# CPU_22032016_v2.net
KiCad netlist of a schematic drawn in Altium Designer
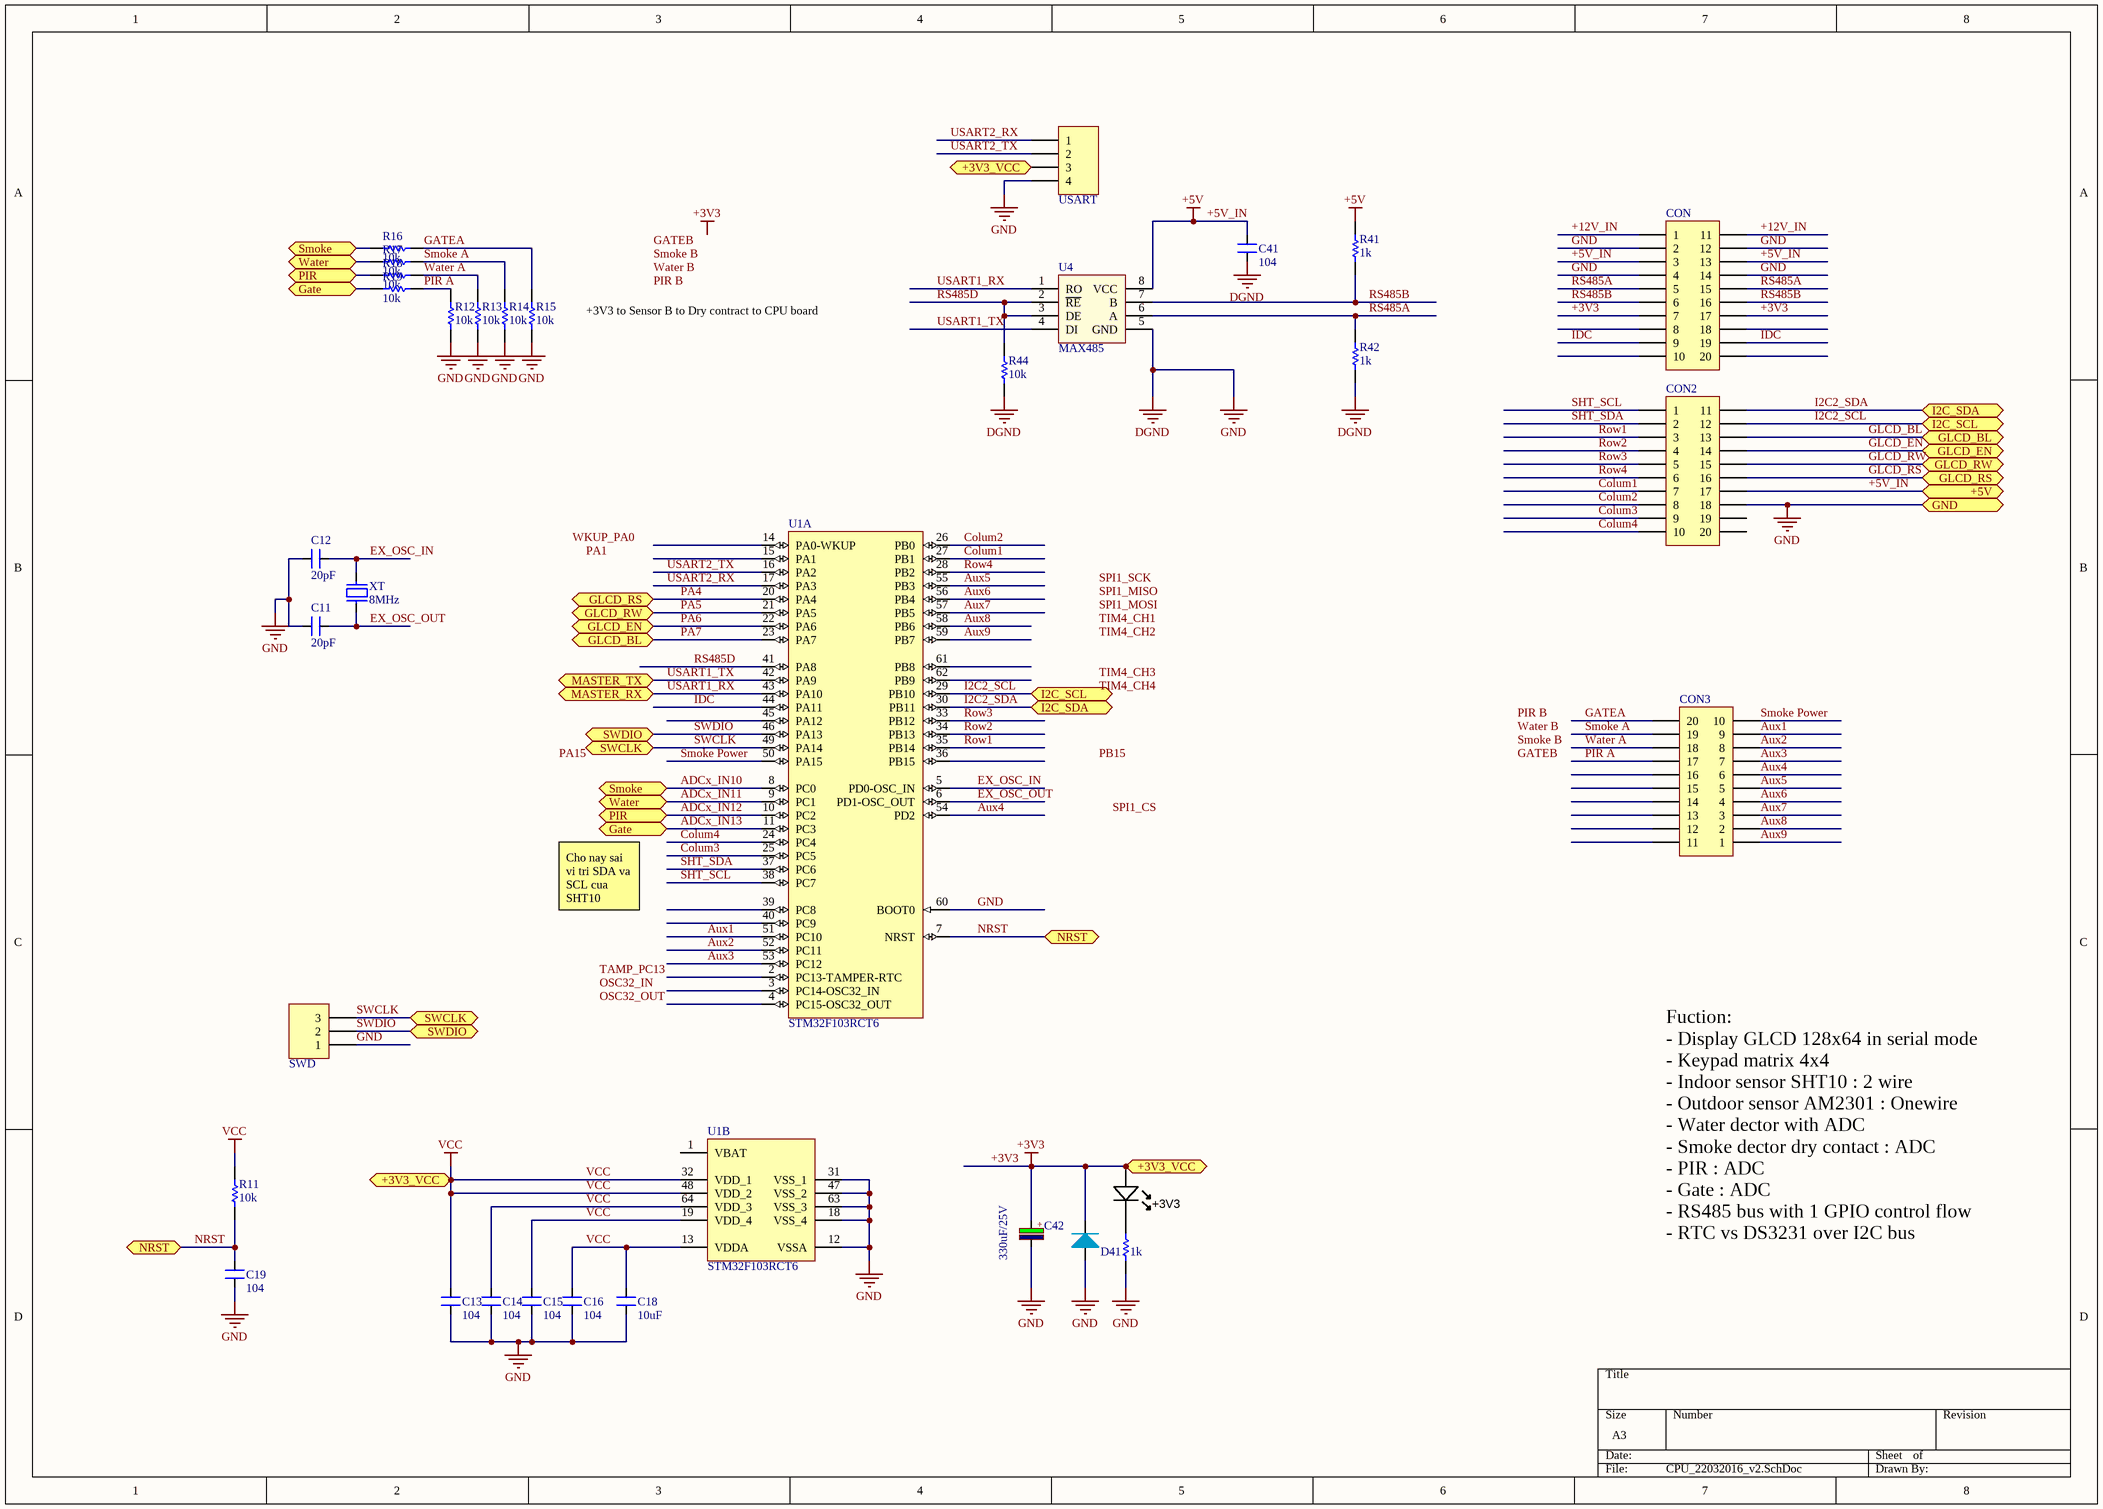
[diagram p0: CPU_22032016_v2.SchDoc]

(export (version "E")
  (design (tool "Eeschema 10.0.6"))
  (components
    (comp (ref "+3V3")
      (value "Blue")
      (footprint "LED-0805-K")
      (description "LED 0805 SMD Blue 100mcd 470nm")
      (libsource (lib "PBL - Light Sources") (part "LED_SMD_Blue_0805_100mcd"))
    )
    (comp (ref "C11")
      (value "20pF")
      (footprint "CAPC1608N")
      (fields (field (name "Comment") "Cap_22p_0603"))
      (libsource (lib "Tuan") (part "CAP NP"))
    )
    (comp (ref "C12")
      (value "20pF")
      (footprint "CAPC1608N")
      (fields (field (name "Comment") "Cap_22p_0603"))
      (libsource (lib "Tuan") (part "CAP NP"))
    )
    (comp (ref "C13")
      (value "104")
      (footprint "CAPC1608N")
      (fields (field (name "Comment") "Cap_104_0603"))
      (libsource (lib "Tuan") (part "CAP NP"))
    )
    (comp (ref "C14")
      (value "104")
      (footprint "CAPC1608N")
      (fields (field (name "Comment") "Cap_104_0603"))
      (libsource (lib "Tuan") (part "CAP NP"))
    )
    (comp (ref "C15")
      (value "104")
      (footprint "CAPC1608N")
      (fields (field (name "Comment") "Cap_104_0603"))
      (libsource (lib "Tuan") (part "CAP NP"))
    )
    (comp (ref "C16")
      (value "104")
      (footprint "CAPC1608N")
      (fields (field (name "Comment") "Cap_104_0603"))
      (libsource (lib "Tuan") (part "CAP NP"))
    )
    (comp (ref "C18")
      (value "10uF")
      (footprint "CAPC2012N_F")
      (fields (field (name "Comment") "Cap_10uF_0805"))
      (libsource (lib "Tuan") (part "CAP NP"))
    )
    (comp (ref "C19")
      (value "104")
      (footprint "CAPC1608N")
      (fields (field (name "Comment") "Cap_104_0603"))
      (libsource (lib "Tuan") (part "CAP NP"))
    )
    (comp (ref "C41")
      (value "104")
      (footprint "CAPC2012N_F")
      (fields (field (name "Comment") "100nF/104"))
      (libsource (lib "Tuan") (part "CAP NP"))
    )
    (comp (ref "C42")
      (value "330uF/25V")
      (footprint "CAPMP3528X210N")
      (description "Cap 1000uF/16V - 220uF/50V")
      (libsource (lib "heromap") (part "CP4"))
    )
    (comp (ref "CON")
      (value "Header 10X2A")
      (footprint "OMC10")
      (description "Header, 10-Pin, Dual row")
      (fields (field (name "PUBLISHER") "Altium Limited"))
      (libsource (lib "Miscellaneous Connectors") (part "Header 10X2A"))
    )
    (comp (ref "CON2")
      (value "Header 10X2A")
      (footprint "OMC10")
      (description "Header, 10-Pin, Dual row")
      (fields (field (name "PUBLISHER") "Altium Limited"))
      (libsource (lib "Miscellaneous Connectors") (part "Header 10X2A"))
    )
    (comp (ref "CON3")
      (value "Header 10X2A")
      (footprint "OMC10")
      (description "Header, 10-Pin, Dual row")
      (fields (field (name "PUBLISHER") "Altium Limited"))
      (libsource (lib "") (part "Header 10X2A_1"))
    )
    (comp (ref "D41") (value "Diode") (footprint "DO-214AC") (libsource (lib "Tuan") (part "Diode")))
    (comp (ref "R11")
      (value "10k")
      (footprint "RESC1608N_F")
      (fields (field (name "Comment") "Res_10k_0603"))
      (libsource (lib "Tuan") (part "Res"))
    )
    (comp (ref "R12")
      (value "10k")
      (footprint "RESC1608N_ZERO")
      (fields (field (name "Comment") "Res"))
      (libsource (lib "Tuan") (part "Res"))
    )
    (comp (ref "R13")
      (value "10k")
      (footprint "RESC1608N_ZERO")
      (fields (field (name "Comment") "Res"))
      (libsource (lib "Tuan") (part "Res"))
    )
    (comp (ref "R14")
      (value "10k")
      (footprint "RESC1608N_ZERO")
      (fields (field (name "Comment") "Res"))
      (libsource (lib "Tuan") (part "Res"))
    )
    (comp (ref "R15")
      (value "10k")
      (footprint "RESC1608N_ZERO")
      (fields (field (name "Comment") "Res"))
      (libsource (lib "Tuan") (part "Res"))
    )
    (comp (ref "R16")
      (value "10k")
      (footprint "RESC1608N_ZERO")
      (fields (field (name "Comment") "Res"))
      (libsource (lib "Tuan") (part "Res"))
    )
    (comp (ref "R17")
      (value "10k")
      (footprint "RESC1608N_ZERO")
      (fields (field (name "Comment") "Res"))
      (libsource (lib "Tuan") (part "Res"))
    )
    (comp (ref "R18")
      (value "10k")
      (footprint "RESC1608N_ZERO")
      (fields (field (name "Comment") "Res"))
      (libsource (lib "Tuan") (part "Res"))
    )
    (comp (ref "R19")
      (value "10k")
      (footprint "RESC1608N_ZERO")
      (fields (field (name "Comment") "Res"))
      (libsource (lib "Tuan") (part "Res"))
    )
    (comp (ref "R41")
      (value "1k")
      (footprint "RESC2012N_F")
      (description "Tro dan")
      (libsource (lib "GPS_Clock_v12") (part "Res"))
    )
    (comp (ref "R42")
      (value "1k")
      (footprint "RESC2012N_F")
      (description "Tro dan")
      (libsource (lib "GPS_Clock_v12") (part "Res"))
    )
    (comp (ref "R44")
      (value "10k")
      (footprint "RESC2012N_F")
      (description "Tro dan")
      (fields (field (name "Comment") "330R"))
      (libsource (lib "GPS_Clock_v12") (part "Res"))
    )
    (comp (ref "Rled")
      (value "1k")
      (footprint "RESC2012N_F")
      (fields (field (name "Comment") "Res_0805_1k"))
      (libsource (lib "Tuan") (part "Res"))
    )
    (comp (ref "SWD")
      (value "Header 3")
      (footprint "heromap:HDR1X3")
      (description "Header, 3-Pin")
      (fields (field (name "PUBLISHER") "Altium Limited"))
      (libsource (lib "heromap") (part "Header 3"))
    )
    (comp (ref "U1")
      (value "STM32F103RCT6")
      (footprint "LQFP64_Tuan")
      (libsource (lib "STMicroelectronics STM32 F1") (part "STM32F103RCT6"))
    )
    (comp (ref "U4")
      (value "MAX485")
      (footprint "SO-8")
      (description "RS232 - RS485 (Same sn75176)")
      (libsource (lib "heromap") (part "MAX485"))
    )
    (comp (ref "USART")
      (value "Header 4")
      (footprint "heromap:HDR1X4")
      (description "Header, 4-Pin")
      (fields (field (name "PUBLISHER") "Altium Limited"))
      (libsource (lib "heromap") (part "Header 4"))
    )
    (comp (ref "XT") (value "8MHz") (footprint "XT2") (libsource (lib "Tuan") (part "Crystal")))
  )
  (nets
    (net (code "1") (name "+3V3") (class "Default")
      (node (ref "+3V3") (pin "A") (pinfunction "A_A") (pintype "passive"))
      (node (ref "C13") (pin "2") (pinfunction "2_2") (pintype "passive"))
      (node (ref "C14") (pin "2") (pinfunction "2_2") (pintype "passive"))
      (node (ref "C15") (pin "2") (pinfunction "2_2") (pintype "passive"))
      (node (ref "C16") (pin "2") (pinfunction "2_2") (pintype "passive"))
      (node (ref "C18") (pin "2") (pinfunction "2_2") (pintype "passive"))
      (node (ref "C42") (pin "1") (pinfunction "1_1") (pintype "passive"))
      (node (ref "CON") (pin "17") (pinfunction "17_17") (pintype "passive"))
      (node (ref "CON") (pin "7") (pinfunction "7_7") (pintype "passive"))
      (node (ref "D41") (pin "2") (pinfunction "K_2") (pintype "passive"))
      (node (ref "R11") (pin "2") (pinfunction "2_2") (pintype "passive"))
      (node (ref "U1") (pin "13") (pinfunction "VDDA_13") (pintype "power_in"))
      (node (ref "U1") (pin "19") (pinfunction "VDD_4_19") (pintype "power_in"))
      (node (ref "U1") (pin "32") (pinfunction "VDD_1_32") (pintype "power_in"))
      (node (ref "U1") (pin "48") (pinfunction "VDD_2_48") (pintype "power_in"))
      (node (ref "U1") (pin "64") (pinfunction "VDD_3_64") (pintype "power_in"))
      (node (ref "USART") (pin "3") (pinfunction "3_3") (pintype "passive"))
    )
    (net (code "2") (name "+5V") (class "Default")
      (node (ref "C41") (pin "2") (pinfunction "2_2") (pintype "passive"))
      (node (ref "CON") (pin "13") (pinfunction "13_13") (pintype "passive"))
      (node (ref "CON") (pin "3") (pinfunction "3_3") (pintype "passive"))
      (node (ref "CON2") (pin "17") (pinfunction "17_17") (pintype "passive"))
      (node (ref "R41") (pin "2") (pinfunction "2_2") (pintype "passive"))
      (node (ref "U4") (pin "8") (pinfunction "VCC_8") (pintype "passive"))
    )
    (net (code "3") (name "/+12V_IN") (class "Default")
      (node (ref "CON") (pin "1") (pinfunction "1_1") (pintype "passive"))
      (node (ref "CON") (pin "11") (pinfunction "11_11") (pintype "passive"))
    )
    (net (code "4") (name "/ADCx_IN10") (class "Default")
      (node (ref "R16") (pin "1") (pinfunction "1_1") (pintype "passive"))
      (node (ref "U1") (pin "8") (pinfunction "PC0_8") (pintype "bidirectional"))
    )
    (net (code "5") (name "/ADCx_IN11") (class "Default")
      (node (ref "R17") (pin "1") (pinfunction "1_1") (pintype "passive"))
      (node (ref "U1") (pin "9") (pinfunction "PC1_9") (pintype "bidirectional"))
    )
    (net (code "6") (name "/ADCx_IN12") (class "Default")
      (node (ref "R18") (pin "1") (pinfunction "1_1") (pintype "passive"))
      (node (ref "U1") (pin "10") (pinfunction "PC2_10") (pintype "bidirectional"))
    )
    (net (code "7") (name "/ADCx_IN13") (class "Default")
      (node (ref "R19") (pin "1") (pinfunction "1_1") (pintype "passive"))
      (node (ref "U1") (pin "11") (pinfunction "PC3_11") (pintype "bidirectional"))
    )
    (net (code "8") (name "/Aux1") (class "Default")
      (node (ref "CON3") (pin "9") (pinfunction "9_9") (pintype "passive"))
      (node (ref "U1") (pin "51") (pinfunction "PC10_51") (pintype "bidirectional"))
    )
    (net (code "9") (name "/Aux2") (class "Default")
      (node (ref "CON3") (pin "8") (pinfunction "8_8") (pintype "passive"))
      (node (ref "U1") (pin "52") (pinfunction "PC11_52") (pintype "bidirectional"))
    )
    (net (code "10") (name "/Aux3") (class "Default")
      (node (ref "CON3") (pin "7") (pinfunction "7_7") (pintype "passive"))
      (node (ref "U1") (pin "53") (pinfunction "PC12_53") (pintype "bidirectional"))
    )
    (net (code "11") (name "/Aux4") (class "Default")
      (node (ref "CON3") (pin "6") (pinfunction "6_6") (pintype "passive"))
      (node (ref "U1") (pin "54") (pinfunction "PD2_54") (pintype "bidirectional"))
    )
    (net (code "12") (name "/Aux5") (class "Default")
      (node (ref "CON3") (pin "5") (pinfunction "5_5") (pintype "passive"))
      (node (ref "U1") (pin "55") (pinfunction "PB3_55") (pintype "bidirectional"))
    )
    (net (code "13") (name "/Aux6") (class "Default")
      (node (ref "CON3") (pin "4") (pinfunction "4_4") (pintype "passive"))
      (node (ref "U1") (pin "56") (pinfunction "PB4_56") (pintype "bidirectional"))
    )
    (net (code "14") (name "/Aux7") (class "Default")
      (node (ref "CON3") (pin "3") (pinfunction "3_3") (pintype "passive"))
      (node (ref "U1") (pin "57") (pinfunction "PB5_57") (pintype "bidirectional"))
    )
    (net (code "15") (name "/Aux8") (class "Default")
      (node (ref "CON3") (pin "2") (pinfunction "2_2") (pintype "passive"))
      (node (ref "U1") (pin "58") (pinfunction "PB6_58") (pintype "bidirectional"))
    )
    (net (code "16") (name "/Aux9") (class "Default")
      (node (ref "CON3") (pin "1") (pinfunction "1_1") (pintype "passive"))
      (node (ref "U1") (pin "59") (pinfunction "PB7_59") (pintype "bidirectional"))
    )
    (net (code "17") (name "/Colum1") (class "Default")
      (node (ref "CON2") (pin "7") (pinfunction "7_7") (pintype "passive"))
      (node (ref "U1") (pin "27") (pinfunction "PB1_27") (pintype "bidirectional"))
    )
    (net (code "18") (name "/Colum2") (class "Default")
      (node (ref "CON2") (pin "8") (pinfunction "8_8") (pintype "passive"))
      (node (ref "U1") (pin "26") (pinfunction "PB0_26") (pintype "bidirectional"))
    )
    (net (code "19") (name "/Colum3") (class "Default")
      (node (ref "CON2") (pin "9") (pinfunction "9_9") (pintype "passive"))
      (node (ref "U1") (pin "25") (pinfunction "PC5_25") (pintype "bidirectional"))
    )
    (net (code "20") (name "/Colum4") (class "Default")
      (node (ref "CON2") (pin "10") (pinfunction "10_10") (pintype "passive"))
      (node (ref "U1") (pin "24") (pinfunction "PC4_24") (pintype "bidirectional"))
    )
    (net (code "21") (name "/EX_OSC_IN") (class "Default")
      (node (ref "C12") (pin "1") (pinfunction "1_1") (pintype "passive"))
      (node (ref "U1") (pin "5") (pinfunction "PD0-OSC_IN_5") (pintype "bidirectional"))
      (node (ref "XT") (pin "2") (pinfunction "2_2") (pintype "passive"))
    )
    (net (code "22") (name "/EX_OSC_OUT") (class "Default")
      (node (ref "C11") (pin "1") (pinfunction "1_1") (pintype "passive"))
      (node (ref "U1") (pin "6") (pinfunction "PD1-OSC_OUT_6") (pintype "bidirectional"))
      (node (ref "XT") (pin "1") (pinfunction "1_1") (pintype "passive"))
    )
    (net (code "23") (name "/GATEA") (class "Default")
      (node (ref "CON3") (pin "20") (pinfunction "20_20") (pintype "passive"))
      (node (ref "R15") (pin "2") (pinfunction "2_2") (pintype "passive"))
      (node (ref "R16") (pin "2") (pinfunction "2_2") (pintype "passive"))
    )
    (net (code "25") (name "/GLCD_BL") (class "Default")
      (node (ref "CON2") (pin "13") (pinfunction "13_13") (pintype "passive"))
      (node (ref "U1") (pin "23") (pinfunction "PA7_23") (pintype "bidirectional"))
    )
    (net (code "26") (name "/GLCD_EN") (class "Default")
      (node (ref "CON2") (pin "14") (pinfunction "14_14") (pintype "passive"))
      (node (ref "U1") (pin "22") (pinfunction "PA6_22") (pintype "bidirectional"))
    )
    (net (code "27") (name "/GLCD_RS") (class "Default")
      (node (ref "CON2") (pin "16") (pinfunction "16_16") (pintype "passive"))
      (node (ref "U1") (pin "20") (pinfunction "PA4_20") (pintype "bidirectional"))
    )
    (net (code "28") (name "/GLCD_RW") (class "Default")
      (node (ref "CON2") (pin "15") (pinfunction "15_15") (pintype "passive"))
      (node (ref "U1") (pin "21") (pinfunction "PA5_21") (pintype "bidirectional"))
    )
    (net (code "29") (name "/I2C2_SCL") (class "Default")
      (node (ref "CON2") (pin "12") (pinfunction "12_12") (pintype "passive"))
      (node (ref "U1") (pin "29") (pinfunction "PB10_29") (pintype "bidirectional"))
    )
    (net (code "30") (name "/I2C2_SDA") (class "Default")
      (node (ref "CON2") (pin "11") (pinfunction "11_11") (pintype "passive"))
      (node (ref "U1") (pin "30") (pinfunction "PB11_30") (pintype "bidirectional"))
    )
    (net (code "31") (name "/IDC") (class "Default")
      (node (ref "CON") (pin "19") (pinfunction "19_19") (pintype "passive"))
      (node (ref "CON") (pin "9") (pinfunction "9_9") (pintype "passive"))
      (node (ref "U1") (pin "44") (pinfunction "PA11_44") (pintype "bidirectional"))
    )
    (net (code "32") (name "/NRST") (class "Default")
      (node (ref "C19") (pin "2") (pinfunction "2_2") (pintype "passive"))
      (node (ref "R11") (pin "1") (pinfunction "1_1") (pintype "passive"))
      (node (ref "U1") (pin "7") (pinfunction "NRST_7") (pintype "bidirectional"))
    )
    (net (code "38") (name "/PIR A") (class "Default")
      (node (ref "CON3") (pin "17") (pinfunction "17_17") (pintype "passive"))
      (node (ref "R12") (pin "1") (pinfunction "1_1") (pintype "passive"))
      (node (ref "R19") (pin "2") (pinfunction "2_2") (pintype "passive"))
    )
    (net (code "40") (name "/RS485A") (class "Default")
      (node (ref "CON") (pin "15") (pinfunction "15_15") (pintype "passive"))
      (node (ref "CON") (pin "5") (pinfunction "5_5") (pintype "passive"))
      (node (ref "R42") (pin "2") (pinfunction "2_2") (pintype "passive"))
      (node (ref "U4") (pin "6") (pinfunction "A_6") (pintype "passive"))
    )
    (net (code "41") (name "/RS485B") (class "Default")
      (node (ref "CON") (pin "16") (pinfunction "16_16") (pintype "passive"))
      (node (ref "CON") (pin "6") (pinfunction "6_6") (pintype "passive"))
      (node (ref "R41") (pin "1") (pinfunction "1_1") (pintype "passive"))
      (node (ref "U4") (pin "7") (pinfunction "B_7") (pintype "passive"))
    )
    (net (code "42") (name "/RS485D") (class "Default")
      (node (ref "R44") (pin "2") (pinfunction "2_2") (pintype "passive"))
      (node (ref "U1") (pin "41") (pinfunction "PA8_41") (pintype "bidirectional"))
      (node (ref "U4") (pin "2") (pinfunction "~{RE}_2") (pintype "passive"))
      (node (ref "U4") (pin "3") (pinfunction "DE_3") (pintype "passive"))
    )
    (net (code "43") (name "/Row1") (class "Default")
      (node (ref "CON2") (pin "3") (pinfunction "3_3") (pintype "passive"))
      (node (ref "U1") (pin "35") (pinfunction "PB14_35") (pintype "bidirectional"))
    )
    (net (code "44") (name "/Row2") (class "Default")
      (node (ref "CON2") (pin "4") (pinfunction "4_4") (pintype "passive"))
      (node (ref "U1") (pin "34") (pinfunction "PB13_34") (pintype "bidirectional"))
    )
    (net (code "45") (name "/Row3") (class "Default")
      (node (ref "CON2") (pin "5") (pinfunction "5_5") (pintype "passive"))
      (node (ref "U1") (pin "33") (pinfunction "PB12_33") (pintype "bidirectional"))
    )
    (net (code "46") (name "/Row4") (class "Default")
      (node (ref "CON2") (pin "6") (pinfunction "6_6") (pintype "passive"))
      (node (ref "U1") (pin "28") (pinfunction "PB2_28") (pintype "bidirectional"))
    )
    (net (code "47") (name "/SHT_SCL") (class "Default")
      (node (ref "CON2") (pin "1") (pinfunction "1_1") (pintype "passive"))
      (node (ref "U1") (pin "38") (pinfunction "PC7_38") (pintype "bidirectional"))
    )
    (net (code "48") (name "/SHT_SDA") (class "Default")
      (node (ref "CON2") (pin "2") (pinfunction "2_2") (pintype "passive"))
      (node (ref "U1") (pin "37") (pinfunction "PC6_37") (pintype "bidirectional"))
    )
    (net (code "53") (name "/SWCLK") (class "Default")
      (node (ref "SWD") (pin "3") (pinfunction "3_3") (pintype "passive"))
      (node (ref "U1") (pin "49") (pinfunction "PA14_49") (pintype "bidirectional"))
    )
    (net (code "54") (name "/SWDIO") (class "Default")
      (node (ref "SWD") (pin "2") (pinfunction "2_2") (pintype "passive"))
      (node (ref "U1") (pin "46") (pinfunction "PA13_46") (pintype "bidirectional"))
    )
    (net (code "55") (name "/Smoke A") (class "Default")
      (node (ref "CON3") (pin "19") (pinfunction "19_19") (pintype "passive"))
      (node (ref "R14") (pin "2") (pinfunction "2_2") (pintype "passive"))
      (node (ref "R17") (pin "2") (pinfunction "2_2") (pintype "passive"))
    )
    (net (code "57") (name "/Smoke Power") (class "Default")
      (node (ref "CON3") (pin "10") (pinfunction "10_10") (pintype "passive"))
      (node (ref "U1") (pin "50") (pinfunction "PA15_50") (pintype "bidirectional"))
    )
    (net (code "63") (name "/USART1_RX") (class "Default")
      (node (ref "U1") (pin "43") (pinfunction "PA10_43") (pintype "bidirectional"))
      (node (ref "U4") (pin "1") (pinfunction "RO_1") (pintype "passive"))
    )
    (net (code "64") (name "/USART1_TX") (class "Default")
      (node (ref "U1") (pin "42") (pinfunction "PA9_42") (pintype "bidirectional"))
      (node (ref "U4") (pin "4") (pinfunction "DI_4") (pintype "passive"))
    )
    (net (code "65") (name "/USART2_RX") (class "Default")
      (node (ref "U1") (pin "17") (pinfunction "PA3_17") (pintype "bidirectional"))
      (node (ref "USART") (pin "1") (pinfunction "1_1") (pintype "passive"))
    )
    (net (code "66") (name "/USART2_TX") (class "Default")
      (node (ref "U1") (pin "16") (pinfunction "PA2_16") (pintype "bidirectional"))
      (node (ref "USART") (pin "2") (pinfunction "2_2") (pintype "passive"))
    )
    (net (code "68") (name "/Water A") (class "Default")
      (node (ref "CON3") (pin "18") (pinfunction "18_18") (pintype "passive"))
      (node (ref "R13") (pin "1") (pinfunction "1_1") (pintype "passive"))
      (node (ref "R18") (pin "2") (pinfunction "2_2") (pintype "passive"))
    )
    (net (code "70") (name "DGND") (class "Default")
      (node (ref "C11") (pin "2") (pinfunction "2_2") (pintype "passive"))
      (node (ref "C12") (pin "2") (pinfunction "2_2") (pintype "passive"))
      (node (ref "C13") (pin "1") (pinfunction "1_1") (pintype "passive"))
      (node (ref "C14") (pin "1") (pinfunction "1_1") (pintype "passive"))
      (node (ref "C15") (pin "1") (pinfunction "1_1") (pintype "passive"))
      (node (ref "C16") (pin "1") (pinfunction "1_1") (pintype "passive"))
      (node (ref "C18") (pin "1") (pinfunction "1_1") (pintype "passive"))
      (node (ref "C19") (pin "1") (pinfunction "1_1") (pintype "passive"))
      (node (ref "C41") (pin "1") (pinfunction "1_1") (pintype "passive"))
      (node (ref "C42") (pin "2") (pinfunction "2_2") (pintype "passive"))
      (node (ref "CON") (pin "12") (pinfunction "12_12") (pintype "passive"))
      (node (ref "CON") (pin "14") (pinfunction "14_14") (pintype "passive"))
      (node (ref "CON") (pin "2") (pinfunction "2_2") (pintype "passive"))
      (node (ref "CON") (pin "4") (pinfunction "4_4") (pintype "passive"))
      (node (ref "CON2") (pin "18") (pinfunction "18_18") (pintype "passive"))
      (node (ref "D41") (pin "1") (pinfunction "A_1") (pintype "passive"))
      (node (ref "R12") (pin "2") (pinfunction "2_2") (pintype "passive"))
      (node (ref "R13") (pin "2") (pinfunction "2_2") (pintype "passive"))
      (node (ref "R14") (pin "1") (pinfunction "1_1") (pintype "passive"))
      (node (ref "R15") (pin "1") (pinfunction "1_1") (pintype "passive"))
      (node (ref "R42") (pin "1") (pinfunction "1_1") (pintype "passive"))
      (node (ref "R44") (pin "1") (pinfunction "1_1") (pintype "passive"))
      (node (ref "Rled") (pin "2") (pinfunction "2_2") (pintype "passive"))
      (node (ref "SWD") (pin "1") (pinfunction "1_1") (pintype "passive"))
      (node (ref "U1") (pin "12") (pinfunction "VSSA_12") (pintype "power_in"))
      (node (ref "U1") (pin "18") (pinfunction "VSS_4_18") (pintype "power_in"))
      (node (ref "U1") (pin "31") (pinfunction "VSS_1_31") (pintype "power_in"))
      (node (ref "U1") (pin "47") (pinfunction "VSS_2_47") (pintype "power_in"))
      (node (ref "U1") (pin "60") (pinfunction "BOOT0_60") (pintype "input"))
      (node (ref "U1") (pin "63") (pinfunction "VSS_3_63") (pintype "power_in"))
      (node (ref "U4") (pin "5") (pinfunction "GND_5") (pintype "passive"))
      (node (ref "USART") (pin "4") (pinfunction "4_4") (pintype "passive"))
    )
    (net (code "71") (name "Net-(+3V3-PadK)") (class "Default")
      (node (ref "+3V3") (pin "K") (pinfunction "K_K") (pintype "passive"))
      (node (ref "Rled") (pin "1") (pinfunction "1_1") (pintype "passive"))
    )
    (net (code "72") (name "unconnected-(CON-Pad8)") (class "Default")
      (node (ref "CON") (pin "8") (pinfunction "8_8") (pintype "passive"))
    )
    (net (code "73") (name "unconnected-(CON-Pad10)") (class "Default")
      (node (ref "CON") (pin "10") (pinfunction "10_10") (pintype "passive"))
    )
    (net (code "74") (name "unconnected-(CON-Pad18)") (class "Default")
      (node (ref "CON") (pin "18") (pinfunction "18_18") (pintype "passive"))
    )
    (net (code "75") (name "unconnected-(CON-Pad20)") (class "Default")
      (node (ref "CON") (pin "20") (pinfunction "20_20") (pintype "passive"))
    )
    (net (code "76") (name "unconnected-(CON2-Pad19)") (class "Default")
      (node (ref "CON2") (pin "19") (pinfunction "19_19") (pintype "passive"))
    )
    (net (code "77") (name "unconnected-(CON2-Pad20)") (class "Default")
      (node (ref "CON2") (pin "20") (pinfunction "20_20") (pintype "passive"))
    )
    (net (code "78") (name "unconnected-(CON3-Pad11)") (class "Default")
      (node (ref "CON3") (pin "11") (pinfunction "11_11") (pintype "passive"))
    )
    (net (code "79") (name "unconnected-(CON3-Pad12)") (class "Default")
      (node (ref "CON3") (pin "12") (pinfunction "12_12") (pintype "passive"))
    )
    (net (code "80") (name "unconnected-(CON3-Pad13)") (class "Default")
      (node (ref "CON3") (pin "13") (pinfunction "13_13") (pintype "passive"))
    )
    (net (code "81") (name "unconnected-(CON3-Pad14)") (class "Default")
      (node (ref "CON3") (pin "14") (pinfunction "14_14") (pintype "passive"))
    )
    (net (code "82") (name "unconnected-(CON3-Pad15)") (class "Default")
      (node (ref "CON3") (pin "15") (pinfunction "15_15") (pintype "passive"))
    )
    (net (code "83") (name "unconnected-(CON3-Pad16)") (class "Default")
      (node (ref "CON3") (pin "16") (pinfunction "16_16") (pintype "passive"))
    )
    (net (code "84") (name "unconnected-(U1A-PA0-WKUP-Pad14)") (class "Default")
      (node (ref "U1") (pin "14") (pinfunction "PA0-WKUP_14") (pintype "bidirectional"))
    )
    (net (code "85") (name "unconnected-(U1A-PA1-Pad15)") (class "Default")
      (node (ref "U1") (pin "15") (pinfunction "PA1_15") (pintype "bidirectional"))
    )
    (net (code "86") (name "unconnected-(U1A-PA12-Pad45)") (class "Default")
      (node (ref "U1") (pin "45") (pinfunction "PA12_45") (pintype "bidirectional"))
    )
    (net (code "87") (name "unconnected-(U1A-PB8-Pad61)") (class "Default")
      (node (ref "U1") (pin "61") (pinfunction "PB8_61") (pintype "bidirectional"))
    )
    (net (code "88") (name "unconnected-(U1A-PB9-Pad62)") (class "Default")
      (node (ref "U1") (pin "62") (pinfunction "PB9_62") (pintype "bidirectional"))
    )
    (net (code "89") (name "unconnected-(U1A-PB15-Pad36)") (class "Default")
      (node (ref "U1") (pin "36") (pinfunction "PB15_36") (pintype "bidirectional"))
    )
    (net (code "90") (name "unconnected-(U1A-PC8-Pad39)") (class "Default")
      (node (ref "U1") (pin "39") (pinfunction "PC8_39") (pintype "bidirectional"))
    )
    (net (code "91") (name "unconnected-(U1A-PC9-Pad40)") (class "Default")
      (node (ref "U1") (pin "40") (pinfunction "PC9_40") (pintype "bidirectional"))
    )
    (net (code "92") (name "unconnected-(U1A-PC13-TAMPER-RTC-Pad2)") (class "Default")
      (node (ref "U1") (pin "2") (pinfunction "PC13-TAMPER-RTC_2") (pintype "bidirectional"))
    )
    (net (code "93") (name "unconnected-(U1A-PC14-OSC32_IN-Pad3)") (class "Default")
      (node (ref "U1") (pin "3") (pinfunction "PC14-OSC32_IN_3") (pintype "bidirectional"))
    )
    (net (code "94") (name "unconnected-(U1A-PC15-OSC32_OUT-Pad4)") (class "Default")
      (node (ref "U1") (pin "4") (pinfunction "PC15-OSC32_OUT_4") (pintype "bidirectional"))
    )
    (net (code "95") (name "unconnected-(U1B-VBAT-Pad1)") (class "Default")
      (node (ref "U1") (pin "1") (pinfunction "VBAT_1") (pintype "power_in"))
    )
  )
)
